# ORCA_Power_Bus.net
KiCad netlist of a schematic drawn in EasyEDA Pro
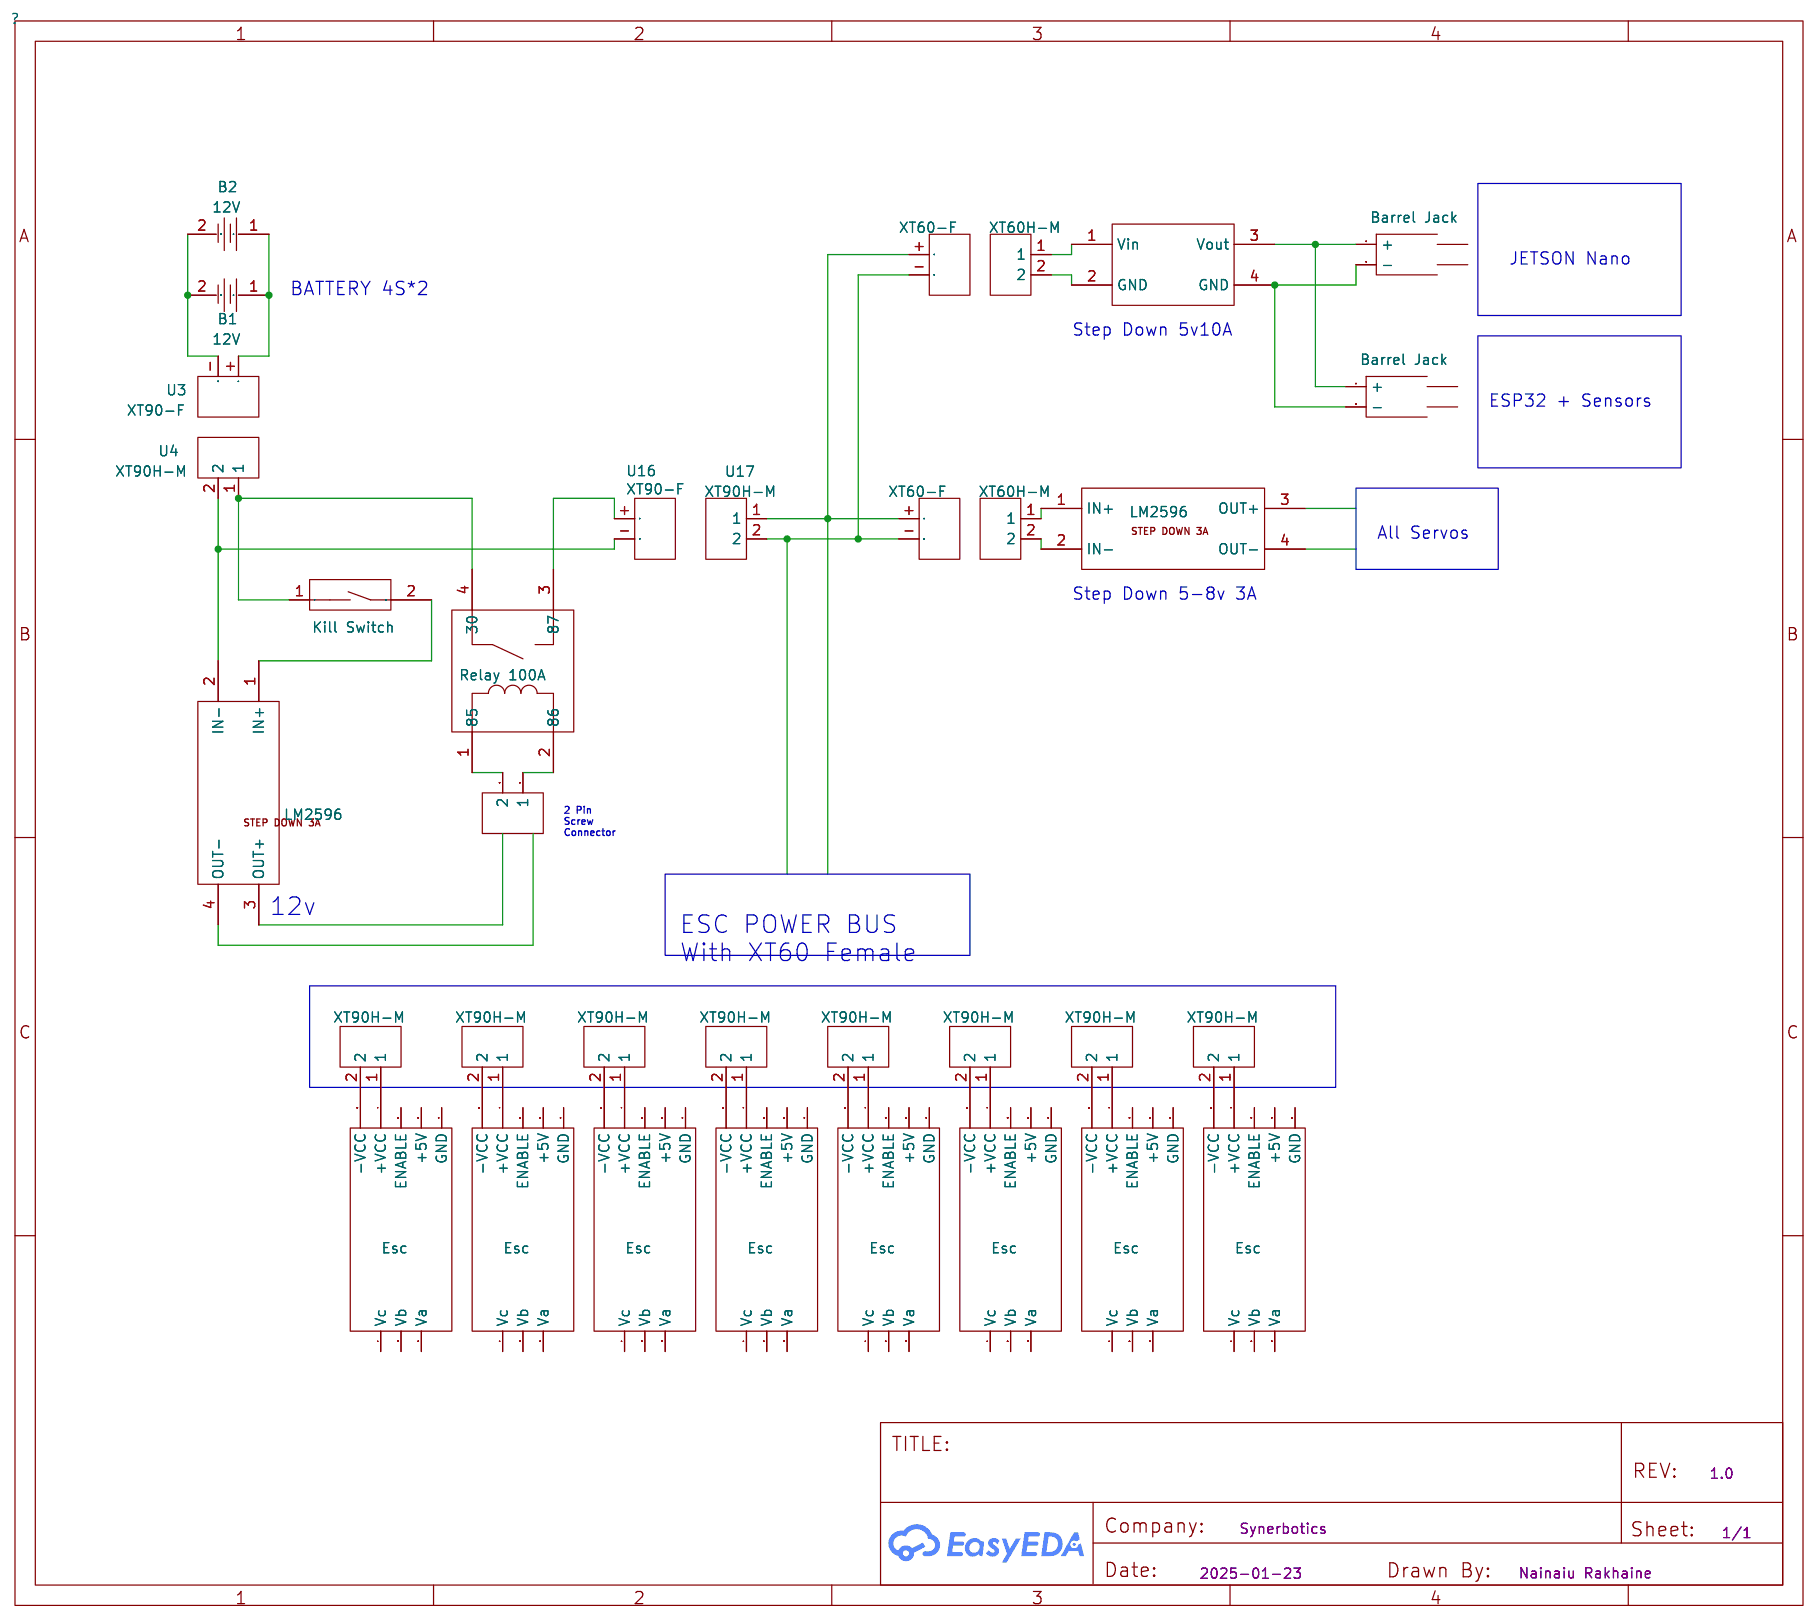
[diagram p0: ORCA Power Circuit]
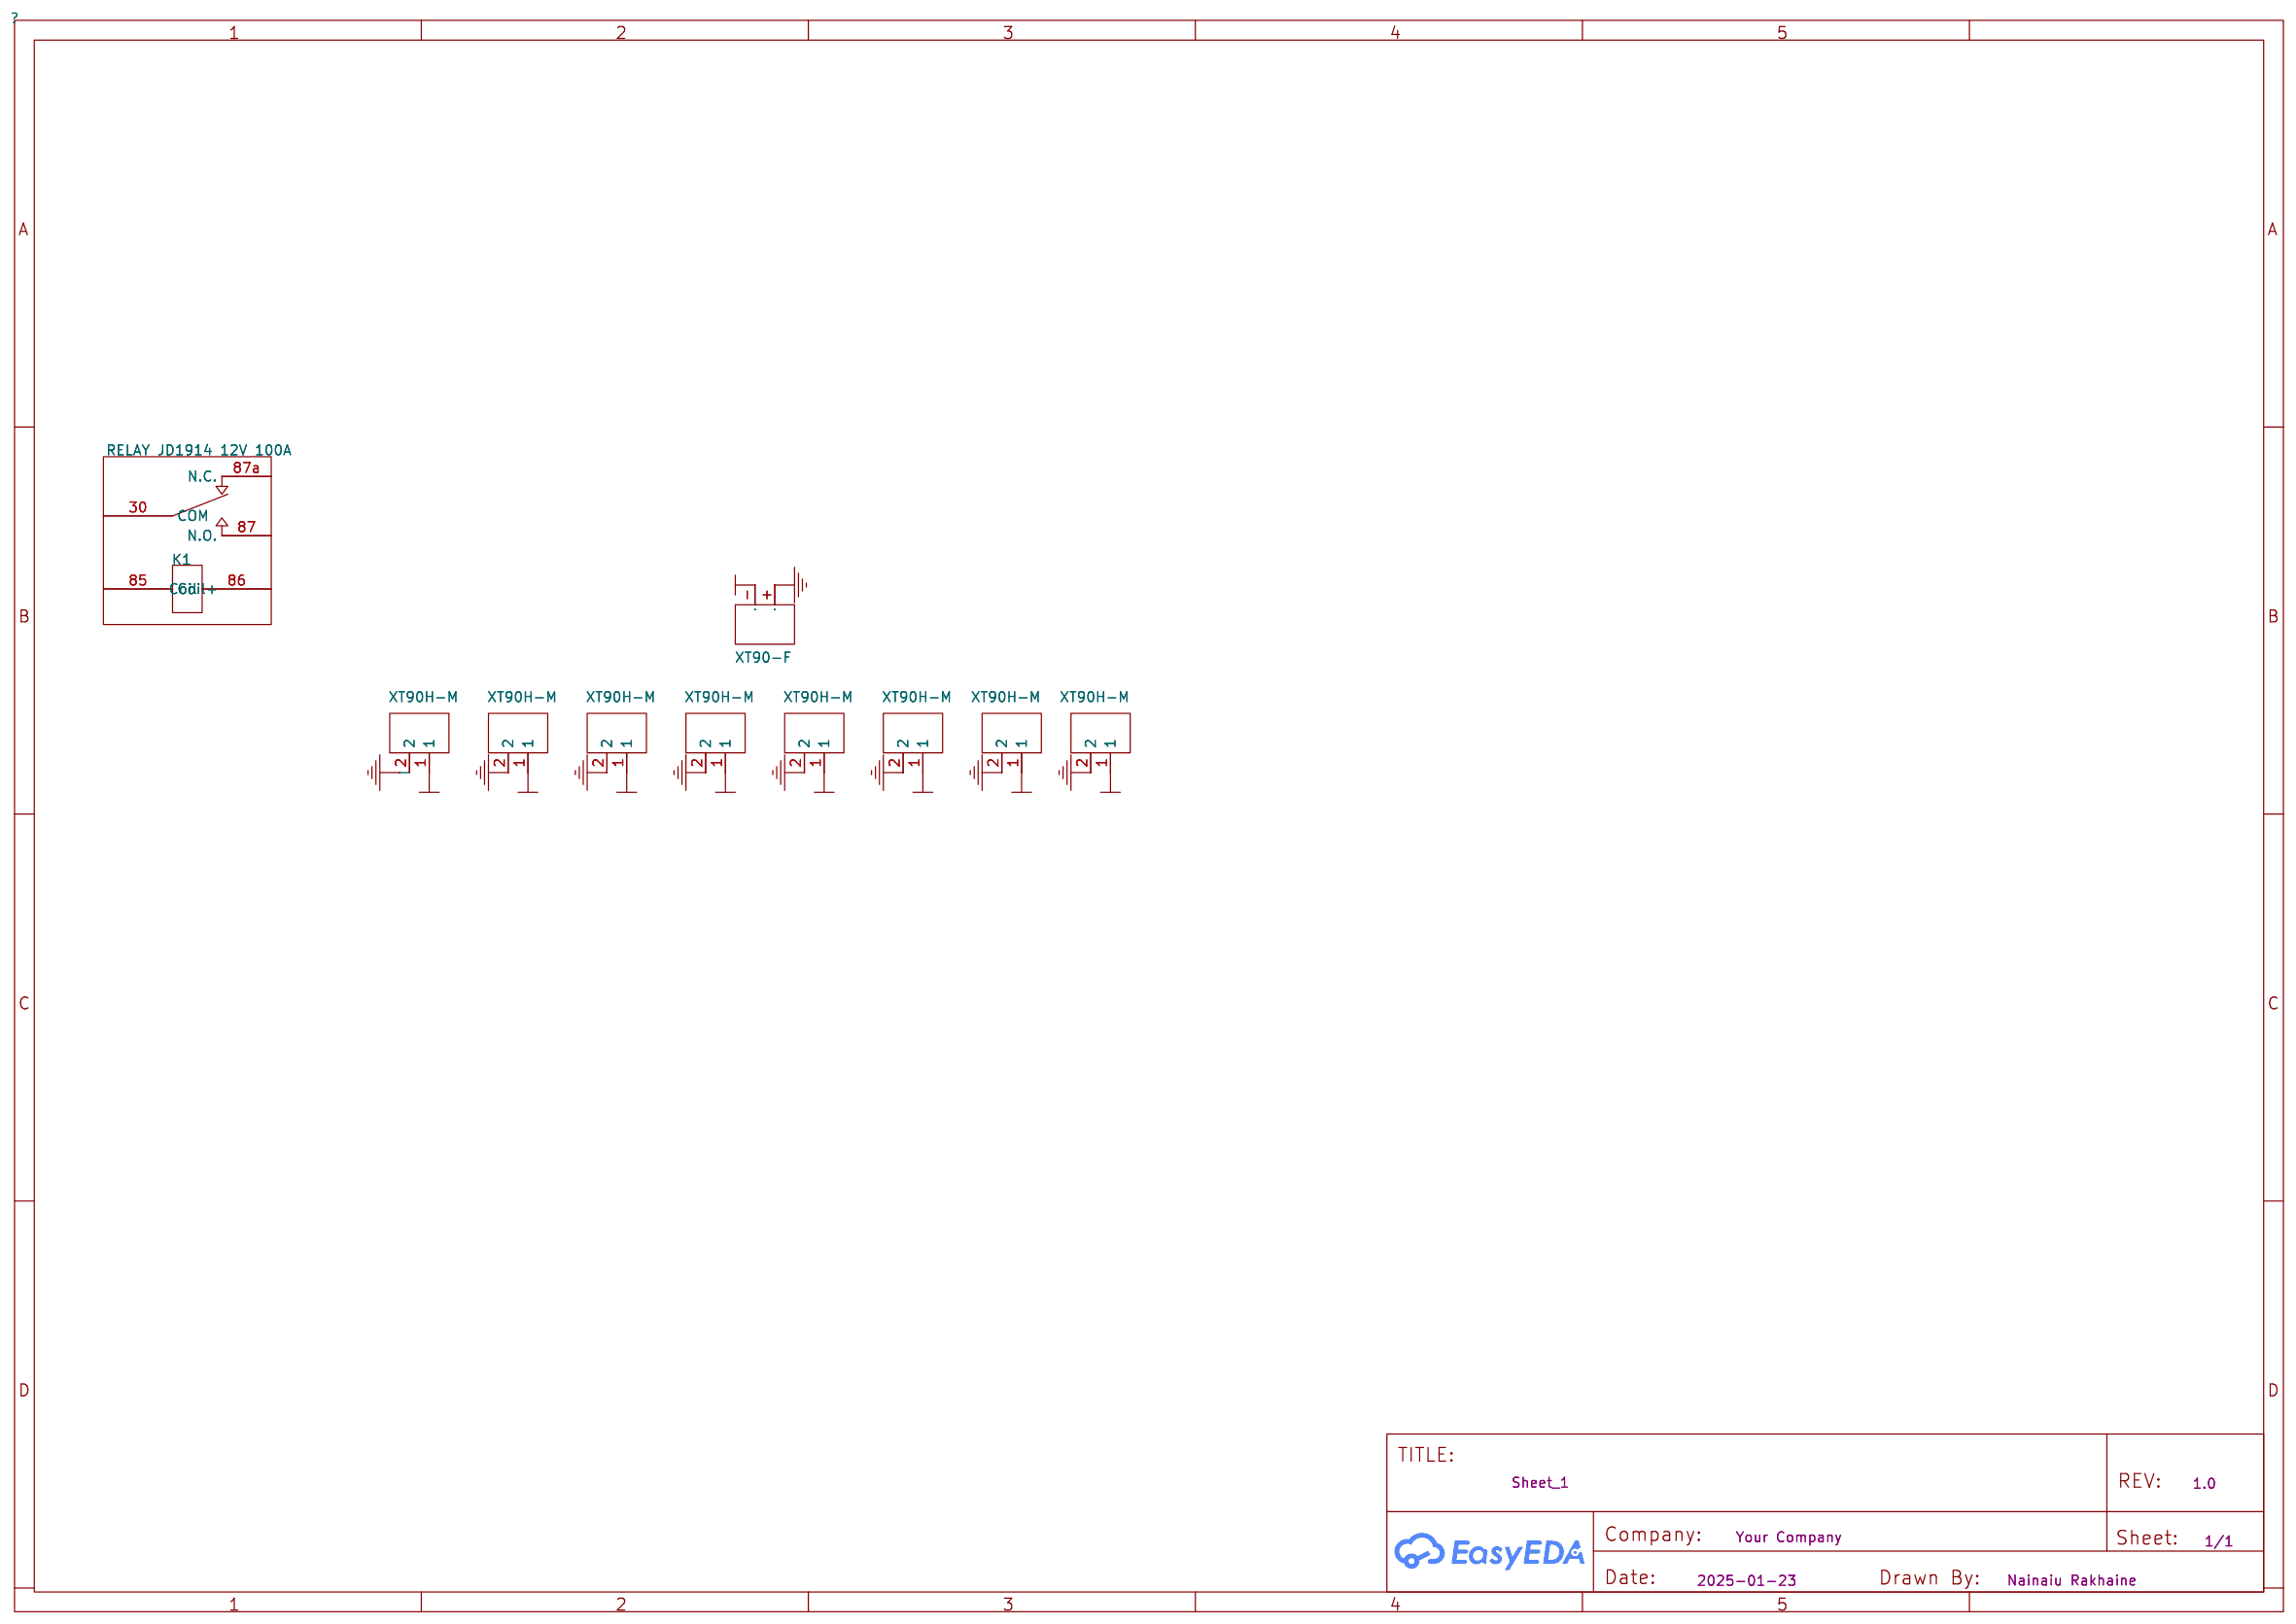
[diagram p1: Sheet_1]

(export (version "E")
  (design (tool "Eeschema 10.0.6"))
  (components
    (comp (ref "2")
      (value "2 PIN TERMINAL BLOCK 5.08 MM")
      (fields
        (field (name "Manufacturer Part") "Screw Terminal Block: 2-Pin")
        (field (name "Manufacturer") "Unknown")
      )
      (libsource (lib "easyedapro") (part "2 PIN TERMINAL BLOCK 5.08 MM"))
    )
    (comp (ref "B1")
      (value "12V")
      (fields (field (name "Manufacturer Part") "BS-2-1") (field (name "Manufacturer") "Q&J"))
      (libsource (lib "easyedapro") (part "12V"))
    )
    (comp (ref "B2")
      (value "12V")
      (fields (field (name "Manufacturer Part") "BS-2-1") (field (name "Manufacturer") "Q&J"))
      (libsource (lib "easyedapro") (part "12V"))
    )
    (comp (ref "DIP1")
      (value "Kill Switch")
      (fields (field (name "Manufacturer Part") "DIP switchEI-08") (field (name "Manufacturer") "DIP"))
      (libsource (lib "easyedapro") (part "Kill Switch"))
    )
    (comp (ref "U1")
      (value "Esc")
      (fields
        (field (name "Manufacturer Part") "ESCS024W150-S-P-F50EC")
        (field (name "Manufacturer") "PowerGood")
      )
      (libsource (lib "easyedapro") (part "Esc"))
    )
    (comp (ref "U2")
      (value "Relay 100A")
      (fields (field (name "Manufacturer Part") "JD2912-1H-12VDC"))
      (libsource (lib "easyedapro") (part "Relay 100A"))
    )
    (comp (ref "U3")
      (value "XT90-F")
      (fields (field (name "Manufacturer Part") "XT60-F") (field (name "Manufacturer") "AMASS(艾迈斯)"))
      (libsource (lib "") (part "XT90-F_1"))
    )
    (comp (ref "U4")
      (value "XT90H-M")
      (fields (field (name "Manufacturer Part") "XT60H-M") (field (name "Manufacturer") "AMASS(艾迈斯)"))
      (libsource (lib "easyedapro") (part "XT90H-M"))
    )
    (comp (ref "U5")
      (value "XT60-F")
      (fields (field (name "Manufacturer") "AMASS(艾迈斯)"))
      (libsource (lib "easyedapro") (part "XT60-F"))
    )
    (comp (ref "U6") (value "Step Down10A") (libsource (lib "easyedapro") (part "Step Down10A")))
    (comp (ref "U7")
      (value "LM2596")
      (fields (field (name "Manufacturer Part") "STEP DOWN 3A") (field (name "Manufacturer") "PEJ"))
      (libsource (lib "easyedapro") (part "LM2596"))
    )
    (comp (ref "U8") (value "Barrel Jack") (libsource (lib "easyedapro") (part "Barrel Jack")))
    (comp (ref "U9")
      (value "Esc")
      (fields
        (field (name "Manufacturer Part") "ESCS024W150-S-P-F50EC")
        (field (name "Manufacturer") "PowerGood")
      )
      (libsource (lib "easyedapro") (part "Esc"))
    )
    (comp (ref "U10")
      (value "Esc")
      (fields
        (field (name "Manufacturer Part") "ESCS024W150-S-P-F50EC")
        (field (name "Manufacturer") "PowerGood")
      )
      (libsource (lib "easyedapro") (part "Esc"))
    )
    (comp (ref "U11")
      (value "Esc")
      (fields
        (field (name "Manufacturer Part") "ESCS024W150-S-P-F50EC")
        (field (name "Manufacturer") "PowerGood")
      )
      (libsource (lib "easyedapro") (part "Esc"))
    )
    (comp (ref "U12")
      (value "Esc")
      (fields
        (field (name "Manufacturer Part") "ESCS024W150-S-P-F50EC")
        (field (name "Manufacturer") "PowerGood")
      )
      (libsource (lib "easyedapro") (part "Esc"))
    )
    (comp (ref "U13")
      (value "Esc")
      (fields
        (field (name "Manufacturer Part") "ESCS024W150-S-P-F50EC")
        (field (name "Manufacturer") "PowerGood")
      )
      (libsource (lib "easyedapro") (part "Esc"))
    )
    (comp (ref "U14")
      (value "Esc")
      (fields
        (field (name "Manufacturer Part") "ESCS024W150-S-P-F50EC")
        (field (name "Manufacturer") "PowerGood")
      )
      (libsource (lib "easyedapro") (part "Esc"))
    )
    (comp (ref "U15")
      (value "Esc")
      (fields
        (field (name "Manufacturer Part") "ESCS024W150-S-P-F50EC")
        (field (name "Manufacturer") "PowerGood")
      )
      (libsource (lib "easyedapro") (part "Esc"))
    )
    (comp (ref "U16")
      (value "XT90-F")
      (fields (field (name "Manufacturer Part") "XT60-F") (field (name "Manufacturer") "AMASS(艾迈斯)"))
      (libsource (lib "easyedapro") (part "XT90-F"))
    )
    (comp (ref "U17")
      (value "XT90H-M")
      (fields (field (name "Manufacturer Part") "XT60H-M") (field (name "Manufacturer") "AMASS(艾迈斯)"))
      (libsource (lib "") (part "XT90H-M_1"))
    )
    (comp (ref "U18")
      (value "XT90H-M")
      (fields (field (name "Manufacturer Part") "XT60H-M") (field (name "Manufacturer") "AMASS(艾迈斯)"))
      (libsource (lib "easyedapro") (part "XT90H-M"))
    )
    (comp (ref "U19")
      (value "XT90H-M")
      (fields (field (name "Manufacturer Part") "XT60H-M") (field (name "Manufacturer") "AMASS(艾迈斯)"))
      (libsource (lib "easyedapro") (part "XT90H-M"))
    )
    (comp (ref "U20")
      (value "XT90H-M")
      (fields (field (name "Manufacturer Part") "XT60H-M") (field (name "Manufacturer") "AMASS(艾迈斯)"))
      (libsource (lib "easyedapro") (part "XT90H-M"))
    )
    (comp (ref "U21")
      (value "XT90H-M")
      (fields (field (name "Manufacturer Part") "XT60H-M") (field (name "Manufacturer") "AMASS(艾迈斯)"))
      (libsource (lib "easyedapro") (part "XT90H-M"))
    )
    (comp (ref "U22")
      (value "XT90H-M")
      (fields (field (name "Manufacturer Part") "XT60H-M") (field (name "Manufacturer") "AMASS(艾迈斯)"))
      (libsource (lib "easyedapro") (part "XT90H-M"))
    )
    (comp (ref "U23")
      (value "XT90H-M")
      (fields (field (name "Manufacturer Part") "XT60H-M") (field (name "Manufacturer") "AMASS(艾迈斯)"))
      (libsource (lib "easyedapro") (part "XT90H-M"))
    )
    (comp (ref "U24")
      (value "XT90H-M")
      (fields (field (name "Manufacturer Part") "XT60H-M") (field (name "Manufacturer") "AMASS(艾迈斯)"))
      (libsource (lib "easyedapro") (part "XT90H-M"))
    )
    (comp (ref "U25")
      (value "XT90H-M")
      (fields (field (name "Manufacturer Part") "XT60H-M") (field (name "Manufacturer") "AMASS(艾迈斯)"))
      (libsource (lib "easyedapro") (part "XT90H-M"))
    )
    (comp (ref "U26")
      (value "XT60-F")
      (fields (field (name "Manufacturer") "AMASS(艾迈斯)"))
      (libsource (lib "easyedapro") (part "XT60-F"))
    )
    (comp (ref "U27")
      (value "XT60H-M")
      (fields (field (name "Manufacturer") "AMASS(艾迈斯)"))
      (libsource (lib "easyedapro") (part "XT60H-M"))
    )
    (comp (ref "U28")
      (value "XT60H-M")
      (fields (field (name "Manufacturer") "AMASS(艾迈斯)"))
      (libsource (lib "easyedapro") (part "XT60H-M"))
    )
    (comp (ref "U29")
      (value "LM2596")
      (fields (field (name "Manufacturer Part") "STEP DOWN 3A") (field (name "Manufacturer") "PEJ"))
      (libsource (lib "") (part "LM2596_1"))
    )
    (comp (ref "U30") (value "Barrel Jack") (libsource (lib "easyedapro") (part "Barrel Jack")))
    (comp (ref "K1")
      (value "RELAY JD1914 12V 100A")
      (footprint "easyedapro:JD1914")
      (fields (field (name "Manufacturer Part") "JD1914") (field (name "Manufacturer") "BenFeng"))
      (libsource (lib "easyedapro") (part "RELAY JD1914 12V 100A"))
    )
    (comp (ref "U31")
      (value "XT90-F")
      (fields (field (name "Manufacturer Part") "XT60-F") (field (name "Manufacturer") "AMASS(艾迈斯)"))
      (libsource (lib "easyedapro") (part "XT90-F"))
    )
    (comp (ref "U32")
      (value "XT90H-M")
      (fields (field (name "Manufacturer Part") "XT60H-M") (field (name "Manufacturer") "AMASS(艾迈斯)"))
      (libsource (lib "easyedapro") (part "XT90H-M"))
    )
    (comp (ref "U33")
      (value "XT90H-M")
      (fields (field (name "Manufacturer Part") "XT60H-M") (field (name "Manufacturer") "AMASS(艾迈斯)"))
      (libsource (lib "easyedapro") (part "XT90H-M"))
    )
    (comp (ref "U34")
      (value "XT90H-M")
      (fields (field (name "Manufacturer Part") "XT60H-M") (field (name "Manufacturer") "AMASS(艾迈斯)"))
      (libsource (lib "easyedapro") (part "XT90H-M"))
    )
    (comp (ref "U35")
      (value "XT90H-M")
      (fields (field (name "Manufacturer Part") "XT60H-M") (field (name "Manufacturer") "AMASS(艾迈斯)"))
      (libsource (lib "easyedapro") (part "XT90H-M"))
    )
    (comp (ref "U36")
      (value "XT90H-M")
      (fields (field (name "Manufacturer Part") "XT60H-M") (field (name "Manufacturer") "AMASS(艾迈斯)"))
      (libsource (lib "easyedapro") (part "XT90H-M"))
    )
    (comp (ref "U37")
      (value "XT90H-M")
      (fields (field (name "Manufacturer Part") "XT60H-M") (field (name "Manufacturer") "AMASS(艾迈斯)"))
      (libsource (lib "easyedapro") (part "XT90H-M"))
    )
    (comp (ref "U38")
      (value "XT90H-M")
      (fields (field (name "Manufacturer Part") "XT60H-M") (field (name "Manufacturer") "AMASS(艾迈斯)"))
      (libsource (lib "easyedapro") (part "XT90H-M"))
    )
    (comp (ref "U39")
      (value "XT90H-M")
      (fields (field (name "Manufacturer Part") "XT60H-M") (field (name "Manufacturer") "AMASS(艾迈斯)"))
      (libsource (lib "easyedapro") (part "XT90H-M"))
    )
  )
  (nets
    (net (code "1") (name "GND") (class "Default")
      (node (ref "U31") (pin "+") (pinfunction "1_+") (pintype "unspecified"))
      (node (ref "U32") (pin "2") (pinfunction "2_2") (pintype "unspecified"))
      (node (ref "U33") (pin "2") (pinfunction "2_2") (pintype "unspecified"))
      (node (ref "U34") (pin "2") (pinfunction "2_2") (pintype "unspecified"))
      (node (ref "U35") (pin "2") (pinfunction "2_2") (pintype "unspecified"))
      (node (ref "U36") (pin "2") (pinfunction "2_2") (pintype "unspecified"))
      (node (ref "U37") (pin "2") (pinfunction "2_2") (pintype "unspecified"))
      (node (ref "U38") (pin "2") (pinfunction "2_2") (pintype "unspecified"))
      (node (ref "U39") (pin "2") (pinfunction "2_2") (pintype "unspecified"))
    )
    (net (code "2") (name "Net-(U1-+VCC)") (class "Default")
      (node (ref "U1") (pin "7") (pinfunction "+VCC_7") (pintype "unspecified"))
      (node (ref "U18") (pin "1") (pinfunction "1_1") (pintype "unspecified"))
    )
    (net (code "3") (name "Net-(U1--VCC)") (class "Default")
      (node (ref "U1") (pin "8") (pinfunction "-VCC_8") (pintype "unspecified"))
      (node (ref "U18") (pin "2") (pinfunction "2_2") (pintype "unspecified"))
    )
    (net (code "4") (name "Net-(U2-30)") (class "Default")
      (node (ref "DIP1") (pin "1") (pinfunction "1_1") (pintype "unspecified"))
      (node (ref "U2") (pin "4") (pinfunction "30_4") (pintype "unspecified"))
      (node (ref "U4") (pin "1") (pinfunction "1_1") (pintype "unspecified"))
    )
    (net (code "5") (name "Net-(U2-85)") (class "Default")
      (node (ref "2") (pin "2") (pinfunction "2_2") (pintype "unspecified"))
      (node (ref "U2") (pin "1") (pinfunction "85_1") (pintype "unspecified"))
    )
    (net (code "6") (name "Net-(U2-86)") (class "Default")
      (node (ref "2") (pin "1") (pinfunction "1_1") (pintype "unspecified"))
      (node (ref "U2") (pin "2") (pinfunction "86_2") (pintype "unspecified"))
    )
    (net (code "7") (name "Net-(U3-1)") (class "Default")
      (node (ref "B1") (pin "1") (pinfunction "1_1") (pintype "unspecified"))
      (node (ref "B2") (pin "1") (pinfunction "1_1") (pintype "unspecified"))
      (node (ref "U3") (pin "+") (pinfunction "1_+") (pintype "unspecified"))
    )
    (net (code "8") (name "Net-(U3-2)") (class "Default")
      (node (ref "B1") (pin "2") (pinfunction "2_2") (pintype "unspecified"))
      (node (ref "B2") (pin "2") (pinfunction "2_2") (pintype "unspecified"))
      (node (ref "U3") (pin "-") (pinfunction "2_-") (pintype "unspecified"))
    )
    (net (code "9") (name "Net-(U6-Vin)") (class "Default")
      (node (ref "U27") (pin "1") (pinfunction "1_1") (pintype "unspecified"))
      (node (ref "U6") (pin "1") (pinfunction "Vin_1") (pintype "unspecified"))
    )
    (net (code "10") (name "Net-(U7-IN+)") (class "Default")
      (node (ref "DIP1") (pin "2") (pinfunction "2_2") (pintype "unspecified"))
      (node (ref "U7") (pin "1") (pinfunction "IN+_1") (pintype "unspecified"))
    )
    (net (code "11") (name "Net-(U9-+VCC)") (class "Default")
      (node (ref "U19") (pin "1") (pinfunction "1_1") (pintype "unspecified"))
      (node (ref "U9") (pin "7") (pinfunction "+VCC_7") (pintype "unspecified"))
    )
    (net (code "12") (name "Net-(U9--VCC)") (class "Default")
      (node (ref "U19") (pin "2") (pinfunction "2_2") (pintype "unspecified"))
      (node (ref "U9") (pin "8") (pinfunction "-VCC_8") (pintype "unspecified"))
    )
    (net (code "13") (name "Net-(U10-+VCC)") (class "Default")
      (node (ref "U10") (pin "7") (pinfunction "+VCC_7") (pintype "unspecified"))
      (node (ref "U20") (pin "1") (pinfunction "1_1") (pintype "unspecified"))
    )
    (net (code "14") (name "Net-(U10--VCC)") (class "Default")
      (node (ref "U10") (pin "8") (pinfunction "-VCC_8") (pintype "unspecified"))
      (node (ref "U20") (pin "2") (pinfunction "2_2") (pintype "unspecified"))
    )
    (net (code "15") (name "Net-(U11-+VCC)") (class "Default")
      (node (ref "U11") (pin "7") (pinfunction "+VCC_7") (pintype "unspecified"))
      (node (ref "U23") (pin "1") (pinfunction "1_1") (pintype "unspecified"))
    )
    (net (code "16") (name "Net-(U11--VCC)") (class "Default")
      (node (ref "U11") (pin "8") (pinfunction "-VCC_8") (pintype "unspecified"))
      (node (ref "U23") (pin "2") (pinfunction "2_2") (pintype "unspecified"))
    )
    (net (code "17") (name "Net-(U12-+VCC)") (class "Default")
      (node (ref "U12") (pin "7") (pinfunction "+VCC_7") (pintype "unspecified"))
      (node (ref "U22") (pin "1") (pinfunction "1_1") (pintype "unspecified"))
    )
    (net (code "18") (name "Net-(U12--VCC)") (class "Default")
      (node (ref "U12") (pin "8") (pinfunction "-VCC_8") (pintype "unspecified"))
      (node (ref "U22") (pin "2") (pinfunction "2_2") (pintype "unspecified"))
    )
    (net (code "19") (name "Net-(U13-+VCC)") (class "Default")
      (node (ref "U13") (pin "7") (pinfunction "+VCC_7") (pintype "unspecified"))
      (node (ref "U21") (pin "1") (pinfunction "1_1") (pintype "unspecified"))
    )
    (net (code "20") (name "Net-(U13--VCC)") (class "Default")
      (node (ref "U13") (pin "8") (pinfunction "-VCC_8") (pintype "unspecified"))
      (node (ref "U21") (pin "2") (pinfunction "2_2") (pintype "unspecified"))
    )
    (net (code "21") (name "Net-(U14-+VCC)") (class "Default")
      (node (ref "U14") (pin "7") (pinfunction "+VCC_7") (pintype "unspecified"))
      (node (ref "U25") (pin "1") (pinfunction "1_1") (pintype "unspecified"))
    )
    (net (code "22") (name "Net-(U14--VCC)") (class "Default")
      (node (ref "U14") (pin "8") (pinfunction "-VCC_8") (pintype "unspecified"))
      (node (ref "U25") (pin "2") (pinfunction "2_2") (pintype "unspecified"))
    )
    (net (code "23") (name "Net-(U15-+VCC)") (class "Default")
      (node (ref "U15") (pin "7") (pinfunction "+VCC_7") (pintype "unspecified"))
      (node (ref "U24") (pin "1") (pinfunction "1_1") (pintype "unspecified"))
    )
    (net (code "24") (name "Net-(U15--VCC)") (class "Default")
      (node (ref "U15") (pin "8") (pinfunction "-VCC_8") (pintype "unspecified"))
      (node (ref "U24") (pin "2") (pinfunction "2_2") (pintype "unspecified"))
    )
    (net (code "25") (name "Net-(U16-1)") (class "Default")
      (node (ref "U16") (pin "+") (pinfunction "1_+") (pintype "unspecified"))
      (node (ref "U2") (pin "3") (pinfunction "87_3") (pintype "unspecified"))
    )
    (net (code "26") (name "Net-(U16-2)") (class "Default")
      (node (ref "U16") (pin "-") (pinfunction "2_-") (pintype "unspecified"))
      (node (ref "U4") (pin "2") (pinfunction "2_2") (pintype "unspecified"))
      (node (ref "U7") (pin "2") (pinfunction "IN-_2") (pintype "unspecified"))
    )
    (net (code "27") (name "Net-(U26-1)") (class "Default")
      (node (ref "U17") (pin "1") (pinfunction "1_1") (pintype "unspecified"))
      (node (ref "U26") (pin "+") (pinfunction "1_+") (pintype "unspecified"))
      (node (ref "U5") (pin "+") (pinfunction "1_+") (pintype "unspecified"))
    )
    (net (code "28") (name "Net-(U26-2)") (class "Default")
      (node (ref "U17") (pin "2") (pinfunction "2_2") (pintype "unspecified"))
      (node (ref "U26") (pin "-") (pinfunction "2_-") (pintype "unspecified"))
      (node (ref "U5") (pin "-") (pinfunction "2_-") (pintype "unspecified"))
    )
    (net (code "29") (name "Net-(U27-Pad2)") (class "Default")
      (node (ref "U27") (pin "2") (pinfunction "2_2") (pintype "unspecified"))
      (node (ref "U6") (pin "2") (pinfunction "GND_2") (pintype "unspecified"))
    )
    (net (code "30") (name "Net-(U29-IN+)") (class "Default")
      (node (ref "U28") (pin "1") (pinfunction "1_1") (pintype "unspecified"))
      (node (ref "U29") (pin "1") (pinfunction "IN+_1") (pintype "unspecified"))
    )
    (net (code "31") (name "Net-(U29-IN-)") (class "Default")
      (node (ref "U28") (pin "2") (pinfunction "2_2") (pintype "unspecified"))
      (node (ref "U29") (pin "2") (pinfunction "IN-_2") (pintype "unspecified"))
    )
    (net (code "32") (name "Net-(U30-+)") (class "Default")
      (node (ref "U30") (pin "1") (pinfunction "+_1") (pintype "unspecified"))
      (node (ref "U6") (pin "3") (pinfunction "Vout_3") (pintype "unspecified"))
      (node (ref "U8") (pin "1") (pinfunction "+_1") (pintype "unspecified"))
    )
    (net (code "33") (name "Net-(U30--)") (class "Default")
      (node (ref "U30") (pin "2") (pinfunction "-_2") (pintype "unspecified"))
      (node (ref "U6") (pin "4") (pinfunction "GND_4") (pintype "unspecified"))
      (node (ref "U8") (pin "2") (pinfunction "-_2") (pintype "unspecified"))
    )
    (net (code "34") (name "VCC") (class "Default")
      (node (ref "U31") (pin "-") (pinfunction "2_-") (pintype "unspecified"))
      (node (ref "U32") (pin "1") (pinfunction "1_1") (pintype "unspecified"))
      (node (ref "U33") (pin "1") (pinfunction "1_1") (pintype "unspecified"))
      (node (ref "U34") (pin "1") (pinfunction "1_1") (pintype "unspecified"))
      (node (ref "U35") (pin "1") (pinfunction "1_1") (pintype "unspecified"))
      (node (ref "U36") (pin "1") (pinfunction "1_1") (pintype "unspecified"))
      (node (ref "U37") (pin "1") (pinfunction "1_1") (pintype "unspecified"))
      (node (ref "U38") (pin "1") (pinfunction "1_1") (pintype "unspecified"))
      (node (ref "U39") (pin "1") (pinfunction "1_1") (pintype "unspecified"))
    )
    (net (code "35") (name "unconnected-(K1-COM-Pad30)") (class "Default")
      (node (ref "K1") (pin "30") (pinfunction "COM_30") (pintype "unspecified"))
    )
    (net (code "36") (name "unconnected-(K1-Coil+-Pad85)") (class "Default")
      (node (ref "K1") (pin "85") (pinfunction "Coil+_85") (pintype "unspecified"))
    )
    (net (code "37") (name "unconnected-(K1-Coil-Pad86)") (class "Default")
      (node (ref "K1") (pin "86") (pinfunction "Coil_86") (pintype "unspecified"))
    )
    (net (code "38") (name "unconnected-(K1-N.C.-Pad87a)") (class "Default")
      (node (ref "K1") (pin "87a") (pinfunction "N.C._87a") (pintype "unspecified"))
    )
    (net (code "39") (name "unconnected-(K1-N.O.-Pad87)") (class "Default")
      (node (ref "K1") (pin "87") (pinfunction "N.O._87") (pintype "unspecified"))
    )
    (net (code "40") (name "unconnected-(U1-+5V-Pad2)") (class "Default")
      (node (ref "U1") (pin "2") (pinfunction "+5V_2") (pintype "unspecified"))
    )
    (net (code "41") (name "unconnected-(U1-ENABLE-Pad3)") (class "Default")
      (node (ref "U1") (pin "3") (pinfunction "ENABLE_3") (pintype "unspecified"))
    )
    (net (code "42") (name "unconnected-(U1-GND-Pad1)") (class "Default")
      (node (ref "U1") (pin "1") (pinfunction "GND_1") (pintype "unspecified"))
    )
    (net (code "43") (name "unconnected-(U1-Va-Pad6)") (class "Default")
      (node (ref "U1") (pin "6") (pinfunction "Va_6") (pintype "unspecified"))
    )
    (net (code "44") (name "unconnected-(U1-Vb-Pad5)") (class "Default")
      (node (ref "U1") (pin "5") (pinfunction "Vb_5") (pintype "unspecified"))
    )
    (net (code "45") (name "unconnected-(U1-Vc-Pad4)") (class "Default")
      (node (ref "U1") (pin "4") (pinfunction "Vc_4") (pintype "unspecified"))
    )
    (net (code "46") (name "unconnected-(U7-OUT+-Pad3)") (class "Default")
      (node (ref "U7") (pin "3") (pinfunction "OUT+_3") (pintype "unspecified"))
    )
    (net (code "47") (name "unconnected-(U7-OUT--Pad4)") (class "Default")
      (node (ref "U7") (pin "4") (pinfunction "OUT-_4") (pintype "unspecified"))
    )
    (net (code "48") (name "unconnected-(U9-+5V-Pad2)") (class "Default")
      (node (ref "U9") (pin "2") (pinfunction "+5V_2") (pintype "unspecified"))
    )
    (net (code "49") (name "unconnected-(U9-ENABLE-Pad3)") (class "Default")
      (node (ref "U9") (pin "3") (pinfunction "ENABLE_3") (pintype "unspecified"))
    )
    (net (code "50") (name "unconnected-(U9-GND-Pad1)") (class "Default")
      (node (ref "U9") (pin "1") (pinfunction "GND_1") (pintype "unspecified"))
    )
    (net (code "51") (name "unconnected-(U9-Va-Pad6)") (class "Default")
      (node (ref "U9") (pin "6") (pinfunction "Va_6") (pintype "unspecified"))
    )
    (net (code "52") (name "unconnected-(U9-Vb-Pad5)") (class "Default")
      (node (ref "U9") (pin "5") (pinfunction "Vb_5") (pintype "unspecified"))
    )
    (net (code "53") (name "unconnected-(U9-Vc-Pad4)") (class "Default")
      (node (ref "U9") (pin "4") (pinfunction "Vc_4") (pintype "unspecified"))
    )
    (net (code "54") (name "unconnected-(U10-+5V-Pad2)") (class "Default")
      (node (ref "U10") (pin "2") (pinfunction "+5V_2") (pintype "unspecified"))
    )
    (net (code "55") (name "unconnected-(U10-ENABLE-Pad3)") (class "Default")
      (node (ref "U10") (pin "3") (pinfunction "ENABLE_3") (pintype "unspecified"))
    )
    (net (code "56") (name "unconnected-(U10-GND-Pad1)") (class "Default")
      (node (ref "U10") (pin "1") (pinfunction "GND_1") (pintype "unspecified"))
    )
    (net (code "57") (name "unconnected-(U10-Va-Pad6)") (class "Default")
      (node (ref "U10") (pin "6") (pinfunction "Va_6") (pintype "unspecified"))
    )
    (net (code "58") (name "unconnected-(U10-Vb-Pad5)") (class "Default")
      (node (ref "U10") (pin "5") (pinfunction "Vb_5") (pintype "unspecified"))
    )
    (net (code "59") (name "unconnected-(U10-Vc-Pad4)") (class "Default")
      (node (ref "U10") (pin "4") (pinfunction "Vc_4") (pintype "unspecified"))
    )
    (net (code "60") (name "unconnected-(U11-+5V-Pad2)") (class "Default")
      (node (ref "U11") (pin "2") (pinfunction "+5V_2") (pintype "unspecified"))
    )
    (net (code "61") (name "unconnected-(U11-ENABLE-Pad3)") (class "Default")
      (node (ref "U11") (pin "3") (pinfunction "ENABLE_3") (pintype "unspecified"))
    )
    (net (code "62") (name "unconnected-(U11-GND-Pad1)") (class "Default")
      (node (ref "U11") (pin "1") (pinfunction "GND_1") (pintype "unspecified"))
    )
    (net (code "63") (name "unconnected-(U11-Va-Pad6)") (class "Default")
      (node (ref "U11") (pin "6") (pinfunction "Va_6") (pintype "unspecified"))
    )
    (net (code "64") (name "unconnected-(U11-Vb-Pad5)") (class "Default")
      (node (ref "U11") (pin "5") (pinfunction "Vb_5") (pintype "unspecified"))
    )
    (net (code "65") (name "unconnected-(U11-Vc-Pad4)") (class "Default")
      (node (ref "U11") (pin "4") (pinfunction "Vc_4") (pintype "unspecified"))
    )
    (net (code "66") (name "unconnected-(U12-+5V-Pad2)") (class "Default")
      (node (ref "U12") (pin "2") (pinfunction "+5V_2") (pintype "unspecified"))
    )
    (net (code "67") (name "unconnected-(U12-ENABLE-Pad3)") (class "Default")
      (node (ref "U12") (pin "3") (pinfunction "ENABLE_3") (pintype "unspecified"))
    )
    (net (code "68") (name "unconnected-(U12-GND-Pad1)") (class "Default")
      (node (ref "U12") (pin "1") (pinfunction "GND_1") (pintype "unspecified"))
    )
    (net (code "69") (name "unconnected-(U12-Va-Pad6)") (class "Default")
      (node (ref "U12") (pin "6") (pinfunction "Va_6") (pintype "unspecified"))
    )
    (net (code "70") (name "unconnected-(U12-Vb-Pad5)") (class "Default")
      (node (ref "U12") (pin "5") (pinfunction "Vb_5") (pintype "unspecified"))
    )
    (net (code "71") (name "unconnected-(U12-Vc-Pad4)") (class "Default")
      (node (ref "U12") (pin "4") (pinfunction "Vc_4") (pintype "unspecified"))
    )
    (net (code "72") (name "unconnected-(U13-+5V-Pad2)") (class "Default")
      (node (ref "U13") (pin "2") (pinfunction "+5V_2") (pintype "unspecified"))
    )
    (net (code "73") (name "unconnected-(U13-ENABLE-Pad3)") (class "Default")
      (node (ref "U13") (pin "3") (pinfunction "ENABLE_3") (pintype "unspecified"))
    )
    (net (code "74") (name "unconnected-(U13-GND-Pad1)") (class "Default")
      (node (ref "U13") (pin "1") (pinfunction "GND_1") (pintype "unspecified"))
    )
    (net (code "75") (name "unconnected-(U13-Va-Pad6)") (class "Default")
      (node (ref "U13") (pin "6") (pinfunction "Va_6") (pintype "unspecified"))
    )
    (net (code "76") (name "unconnected-(U13-Vb-Pad5)") (class "Default")
      (node (ref "U13") (pin "5") (pinfunction "Vb_5") (pintype "unspecified"))
    )
    (net (code "77") (name "unconnected-(U13-Vc-Pad4)") (class "Default")
      (node (ref "U13") (pin "4") (pinfunction "Vc_4") (pintype "unspecified"))
    )
    (net (code "78") (name "unconnected-(U14-+5V-Pad2)") (class "Default")
      (node (ref "U14") (pin "2") (pinfunction "+5V_2") (pintype "unspecified"))
    )
    (net (code "79") (name "unconnected-(U14-ENABLE-Pad3)") (class "Default")
      (node (ref "U14") (pin "3") (pinfunction "ENABLE_3") (pintype "unspecified"))
    )
    (net (code "80") (name "unconnected-(U14-GND-Pad1)") (class "Default")
      (node (ref "U14") (pin "1") (pinfunction "GND_1") (pintype "unspecified"))
    )
    (net (code "81") (name "unconnected-(U14-Va-Pad6)") (class "Default")
      (node (ref "U14") (pin "6") (pinfunction "Va_6") (pintype "unspecified"))
    )
    (net (code "82") (name "unconnected-(U14-Vb-Pad5)") (class "Default")
      (node (ref "U14") (pin "5") (pinfunction "Vb_5") (pintype "unspecified"))
    )
    (net (code "83") (name "unconnected-(U14-Vc-Pad4)") (class "Default")
      (node (ref "U14") (pin "4") (pinfunction "Vc_4") (pintype "unspecified"))
    )
    (net (code "84") (name "unconnected-(U15-+5V-Pad2)") (class "Default")
      (node (ref "U15") (pin "2") (pinfunction "+5V_2") (pintype "unspecified"))
    )
    (net (code "85") (name "unconnected-(U15-ENABLE-Pad3)") (class "Default")
      (node (ref "U15") (pin "3") (pinfunction "ENABLE_3") (pintype "unspecified"))
    )
    (net (code "86") (name "unconnected-(U15-GND-Pad1)") (class "Default")
      (node (ref "U15") (pin "1") (pinfunction "GND_1") (pintype "unspecified"))
    )
    (net (code "87") (name "unconnected-(U15-Va-Pad6)") (class "Default")
      (node (ref "U15") (pin "6") (pinfunction "Va_6") (pintype "unspecified"))
    )
    (net (code "88") (name "unconnected-(U15-Vb-Pad5)") (class "Default")
      (node (ref "U15") (pin "5") (pinfunction "Vb_5") (pintype "unspecified"))
    )
    (net (code "89") (name "unconnected-(U15-Vc-Pad4)") (class "Default")
      (node (ref "U15") (pin "4") (pinfunction "Vc_4") (pintype "unspecified"))
    )
    (net (code "90") (name "unconnected-(U29-OUT+-Pad3)") (class "Default")
      (node (ref "U29") (pin "3") (pinfunction "OUT+_3") (pintype "unspecified"))
    )
    (net (code "91") (name "unconnected-(U29-OUT--Pad4)") (class "Default")
      (node (ref "U29") (pin "4") (pinfunction "OUT-_4") (pintype "unspecified"))
    )
  )
)
